# Schematic.net
KiCad netlist of a schematic drawn in Altium Designer
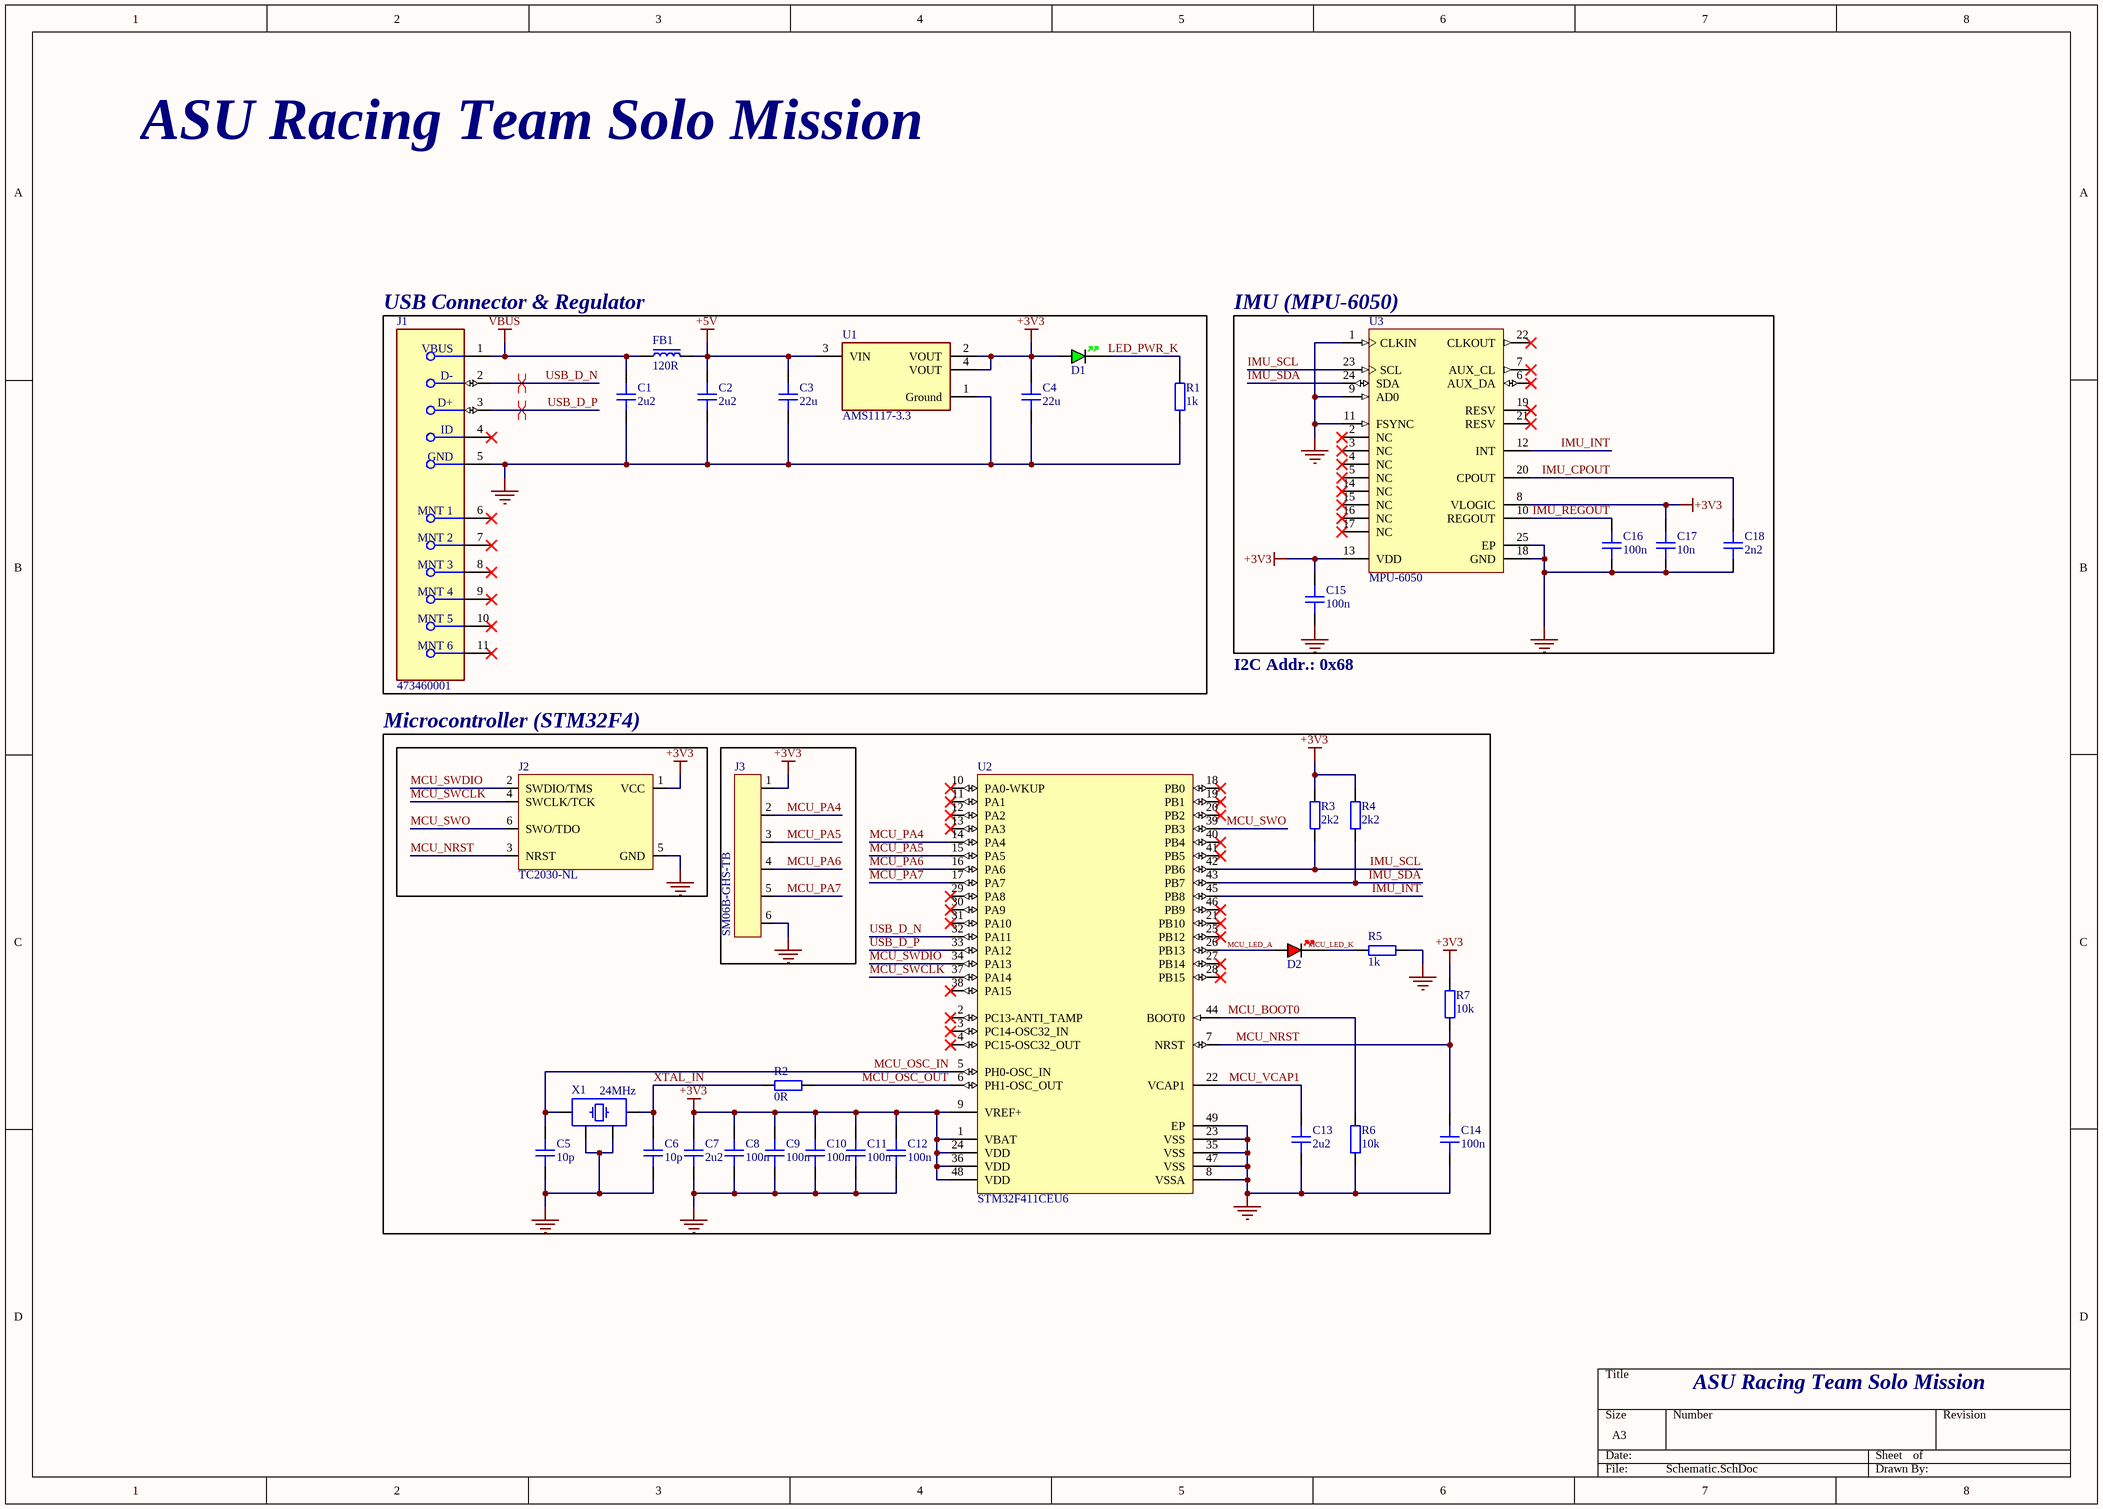
[diagram p0: Schematic.SchDoc]

(export (version "E")
  (design (tool "Eeschema 10.0.6"))
  (components
    (comp (ref "C1")
      (value "2u2")
      (footprint "CAP_0603")
      (description "Capacitor SMD 0603")
      (libsource (lib "Schematic-Lib-PhilsLab") (part "CAP_0603"))
    )
    (comp (ref "C2")
      (value "2u2")
      (footprint "CAP_0603")
      (description "Capacitor SMD 0603")
      (libsource (lib "Schematic-Lib-PhilsLab") (part "CAP_0603"))
    )
    (comp (ref "C3")
      (value "22u")
      (footprint "CAP_0805")
      (description "Capacitor SMD 0805")
      (libsource (lib "Schematic-Lib-PhilsLab") (part "CAP_0805"))
    )
    (comp (ref "C4")
      (value "22u")
      (footprint "CAP_0805")
      (description "Capacitor SMD 0805")
      (libsource (lib "Schematic-Lib-PhilsLab") (part "CAP_0805"))
    )
    (comp (ref "C5")
      (value "10p")
      (footprint "CAP_0402")
      (description "Capacitor SMD 0402")
      (libsource (lib "Schematic-Lib-PhilsLab") (part "CAP_0402"))
    )
    (comp (ref "C6")
      (value "10p")
      (footprint "CAP_0402")
      (description "Capacitor SMD 0402")
      (libsource (lib "Schematic-Lib-PhilsLab") (part "CAP_0402"))
    )
    (comp (ref "C7")
      (value "2u2")
      (footprint "CAP_0603")
      (description "Capacitor SMD 0603")
      (libsource (lib "Schematic-Lib-PhilsLab") (part "CAP_0603"))
    )
    (comp (ref "C8")
      (value "100n")
      (footprint "CAP_0402")
      (description "Capacitor SMD 0402")
      (libsource (lib "Schematic-Lib-PhilsLab") (part "CAP_0402"))
    )
    (comp (ref "C9")
      (value "100n")
      (footprint "CAP_0402")
      (description "Capacitor SMD 0402")
      (libsource (lib "Schematic-Lib-PhilsLab") (part "CAP_0402"))
    )
    (comp (ref "C10")
      (value "100n")
      (footprint "CAP_0402")
      (description "Capacitor SMD 0402")
      (libsource (lib "Schematic-Lib-PhilsLab") (part "CAP_0402"))
    )
    (comp (ref "C11")
      (value "100n")
      (footprint "CAP_0402")
      (description "Capacitor SMD 0402")
      (libsource (lib "Schematic-Lib-PhilsLab") (part "CAP_0402"))
    )
    (comp (ref "C12")
      (value "100n")
      (footprint "CAP_0402")
      (description "Capacitor SMD 0402")
      (libsource (lib "Schematic-Lib-PhilsLab") (part "CAP_0402"))
    )
    (comp (ref "C13")
      (value "2u2")
      (footprint "CAP_0603")
      (description "Capacitor SMD 0603")
      (libsource (lib "Schematic-Lib-PhilsLab") (part "CAP_0603"))
    )
    (comp (ref "C14")
      (value "100n")
      (footprint "CAP_0402")
      (description "Capacitor SMD 0402")
      (libsource (lib "Schematic-Lib-PhilsLab") (part "CAP_0402"))
    )
    (comp (ref "C15")
      (value "100n")
      (footprint "CAP_0402")
      (description "Capacitor SMD 0402")
      (libsource (lib "Schematic-Lib-PhilsLab") (part "CAP_0402"))
    )
    (comp (ref "C16")
      (value "100n")
      (footprint "CAP_0402")
      (description "Capacitor SMD 0402")
      (libsource (lib "Schematic-Lib-PhilsLab") (part "CAP_0402"))
    )
    (comp (ref "C17")
      (value "10n")
      (footprint "CAP_0402")
      (description "Capacitor SMD 0402")
      (libsource (lib "Schematic-Lib-PhilsLab") (part "CAP_0402"))
    )
    (comp (ref "C18")
      (value "2n2")
      (footprint "CAP_0402")
      (description "Capacitor SMD 0402")
      (libsource (lib "Schematic-Lib-PhilsLab") (part "CAP_0402"))
    )
    (comp (ref "D1")
      (value "GREEN")
      (footprint "LED_0402_GREEN")
      (description "LED 0402 GREEN SMD")
      (libsource (lib "Schematic-Lib-PhilsLab") (part "LED_0402_GREEN"))
    )
    (comp (ref "D2")
      (value "RED")
      (footprint "LED_0402_RED")
      (description "LED 0402 RED SMD")
      (libsource (lib "Schematic-Lib-PhilsLab") (part "LED_0402_RED"))
    )
    (comp (ref "FB1")
      (value "120R")
      (footprint "FB_0603")
      (description "Ferrite Bead SMD 0603")
      (libsource (lib "Schematic-Lib-PhilsLab") (part "FB_0603"))
    )
    (comp (ref "J1")
      (value "473460001")
      (footprint "FP-473460001-MFG")
      (description "USB - micro B USB 2.0 Receptacle Connector 5 Position Surface Mount, Right Angle")
      (fields (field (name "OCTOPART") "https://octopart.com/47346-0001-molex-7164928"))
      (libsource (lib "Altium Content Vault") (part "53ae1f1d9b557310b43ca686e5bb76a"))
    )
    (comp (ref "J2")
      (value "TC2030-NL")
      (footprint "TC2030-NL-FP")
      (description "Tag-Connect No-Solder SWD Debug Connector (No Legs) DO NOT PLACE")
      (fields
        (field (name "MANUFACTURER") "Tag-Connect")
        (field (name "MANUFACTURER PART NUMBER") "TC2030-NL-FP")
      )
      (libsource (lib "Schematic-Lib-PhilsLab") (part "TC2030-NL"))
    )
    (comp (ref "J3")
      (value "SM06B-GHS-TB")
      (footprint "SM06B-GHS-TB")
      (description "Header Connector 6 Position 1.25MM Pitch SMD Horizontal JST GH")
      (fields (field (name "MANUFACTURER") "JST"))
      (libsource (lib "Schematic-Lib-PhilsLab") (part "SM06B-GHS-TB"))
    )
    (comp (ref "R1")
      (value "1k")
      (footprint "RES_0402")
      (description "Resistor SMD 0402")
      (libsource (lib "Schematic-Lib-PhilsLab") (part "RES_0402"))
    )
    (comp (ref "R2")
      (value "0R")
      (footprint "RES_0402")
      (description "Resistor SMD 0402")
      (libsource (lib "Schematic-Lib-PhilsLab") (part "RES_0402"))
    )
    (comp (ref "R3")
      (value "2k2")
      (footprint "RES_0402")
      (description "Resistor SMD 0402")
      (libsource (lib "Schematic-Lib-PhilsLab") (part "RES_0402"))
    )
    (comp (ref "R4")
      (value "2k2")
      (footprint "RES_0402")
      (description "Resistor SMD 0402")
      (libsource (lib "Schematic-Lib-PhilsLab") (part "RES_0402"))
    )
    (comp (ref "R5")
      (value "1k")
      (footprint "RES_0402")
      (description "Resistor SMD 0402")
      (libsource (lib "Schematic-Lib-PhilsLab") (part "RES_0402"))
    )
    (comp (ref "R6")
      (value "10k")
      (footprint "RES_0402")
      (description "Resistor SMD 0402")
      (libsource (lib "Schematic-Lib-PhilsLab") (part "RES_0402"))
    )
    (comp (ref "R7")
      (value "10k")
      (footprint "RES_0402")
      (description "Resistor SMD 0402")
      (libsource (lib "Schematic-Lib-PhilsLab") (part "RES_0402"))
    )
    (comp (ref "U1")
      (value "AMS1117-3.3")
      (footprint "FP-AMS1117-IPC_C")
      (description "LDO Voltage Regulators 1A, 3.3V")
      (fields
        (field (name "OCTOPART") "https://octopart.com/ams1117-3.3-advanced+monolithic+systems-25899300")
        (field (name "MANUFACTURER") "Advanced Monolithic Systems")
      )
      (libsource (lib "Altium Content Vault") (part "8bdbb5f8e77002000e30dd2845d0354"))
    )
    (comp (ref "U2")
      (value "STM32F411CEU6")
      (footprint "STM-UFQFPN48_L")
      (libsource (lib "Altium Content Vault") (part "MC-ARM-STM32F411-UFQFPN48"))
    )
    (comp (ref "U3")
      (value "MPU-6050")
      (footprint "IS-QFN-24_V")
      (fields (field (name "MANUFACTURER") "InvenSense"))
      (libsource (lib "Altium Content Vault") (part "IS-MPU-6050-QFN-24"))
    )
    (comp (ref "X1")
      (value "24MHz")
      (footprint "XTAL_3225")
      (description "Crystal SMD 24MHz 10PPM 7pF 3225")
      (fields
        (field (name "MANUFACTURER") "Epson")
        (field (name "MANUFACTURER PART NUMBER") "TSX-3225 24.0000MF15X-AC")
      )
      (libsource (lib "Schematic-Lib-PhilsLab") (part "TSX-3225_24.0000MF15X-AC"))
    )
  )
  (nets
    (net (code "1") (name "+3V3") (class "Default")
      (node (ref "C10") (pin "2") (pinfunction "2_2") (pintype "passive"))
      (node (ref "C11") (pin "2") (pinfunction "2_2") (pintype "passive"))
      (node (ref "C12") (pin "2") (pinfunction "2_2") (pintype "passive"))
      (node (ref "C15") (pin "2") (pinfunction "2_2") (pintype "passive"))
      (node (ref "C17") (pin "2") (pinfunction "2_2") (pintype "passive"))
      (node (ref "C4") (pin "2") (pinfunction "2_2") (pintype "passive"))
      (node (ref "C7") (pin "2") (pinfunction "2_2") (pintype "passive"))
      (node (ref "C8") (pin "2") (pinfunction "2_2") (pintype "passive"))
      (node (ref "C9") (pin "2") (pinfunction "2_2") (pintype "passive"))
      (node (ref "D1") (pin "A") (pinfunction "A_A") (pintype "passive"))
      (node (ref "J2") (pin "1") (pinfunction "VCC_1") (pintype "passive"))
      (node (ref "J3") (pin "1") (pinfunction "1_1") (pintype "passive"))
      (node (ref "R3") (pin "2") (pinfunction "2_2") (pintype "passive"))
      (node (ref "R4") (pin "2") (pinfunction "2_2") (pintype "passive"))
      (node (ref "R7") (pin "2") (pinfunction "2_2") (pintype "passive"))
      (node (ref "U1") (pin "2") (pinfunction "VOUT_2") (pintype "passive"))
      (node (ref "U1") (pin "4") (pinfunction "VOUT_4") (pintype "passive"))
      (node (ref "U2") (pin "1") (pinfunction "VBAT_1") (pintype "power_in"))
      (node (ref "U2") (pin "24") (pinfunction "VDD_24") (pintype "power_in"))
      (node (ref "U2") (pin "36") (pinfunction "VDD_36") (pintype "power_in"))
      (node (ref "U2") (pin "48") (pinfunction "VDD_48") (pintype "power_in"))
      (node (ref "U2") (pin "9") (pinfunction "VREF+_9") (pintype "power_in"))
      (node (ref "U3") (pin "13") (pinfunction "VDD_13") (pintype "power_in"))
      (node (ref "U3") (pin "8") (pinfunction "VLOGIC_8") (pintype "power_in"))
    )
    (net (code "2") (name "+5V") (class "Default")
      (node (ref "C2") (pin "2") (pinfunction "2_2") (pintype "passive"))
      (node (ref "C3") (pin "2") (pinfunction "2_2") (pintype "passive"))
      (node (ref "FB1") (pin "2") (pinfunction "2_2") (pintype "passive"))
      (node (ref "U1") (pin "3") (pinfunction "VIN_3") (pintype "power_in"))
    )
    (net (code "3") (name "/IMU_CPOUT") (class "Default")
      (node (ref "C18") (pin "2") (pinfunction "2_2") (pintype "passive"))
      (node (ref "U3") (pin "20") (pinfunction "CPOUT_20") (pintype "passive"))
    )
    (net (code "4") (name "/IMU_INT") (class "Default")
      (node (ref "U2") (pin "45") (pinfunction "PB8_45") (pintype "bidirectional"))
      (node (ref "U3") (pin "12") (pinfunction "INT_12") (pintype "open_collector"))
    )
    (net (code "5") (name "/IMU_REGOUT") (class "Default")
      (node (ref "C16") (pin "2") (pinfunction "2_2") (pintype "passive"))
      (node (ref "U3") (pin "10") (pinfunction "REGOUT_10") (pintype "passive"))
    )
    (net (code "6") (name "/IMU_SCL") (class "Default")
      (node (ref "R3") (pin "1") (pinfunction "1_1") (pintype "passive"))
      (node (ref "U2") (pin "42") (pinfunction "PB6_42") (pintype "bidirectional"))
      (node (ref "U3") (pin "23") (pinfunction "SCL_23") (pintype "input"))
    )
    (net (code "7") (name "/IMU_SDA") (class "Default")
      (node (ref "R4") (pin "1") (pinfunction "1_1") (pintype "passive"))
      (node (ref "U2") (pin "43") (pinfunction "PB7_43") (pintype "bidirectional"))
      (node (ref "U3") (pin "24") (pinfunction "SDA_24") (pintype "bidirectional"))
    )
    (net (code "8") (name "/LED_PWR_K") (class "Default")
      (node (ref "D1") (pin "K") (pinfunction "K_K") (pintype "passive"))
      (node (ref "R1") (pin "2") (pinfunction "2_2") (pintype "passive"))
    )
    (net (code "9") (name "/MCU_BOOT0") (class "Default")
      (node (ref "R6") (pin "2") (pinfunction "2_2") (pintype "passive"))
      (node (ref "U2") (pin "44") (pinfunction "BOOT0_44") (pintype "input"))
    )
    (net (code "10") (name "/MCU_LED_A") (class "Default")
      (node (ref "D2") (pin "A") (pinfunction "A_A") (pintype "passive"))
      (node (ref "U2") (pin "26") (pinfunction "PB13_26") (pintype "bidirectional"))
    )
    (net (code "11") (name "/MCU_LED_K") (class "Default")
      (node (ref "D2") (pin "K") (pinfunction "K_K") (pintype "passive"))
      (node (ref "R5") (pin "2") (pinfunction "2_2") (pintype "passive"))
    )
    (net (code "12") (name "/MCU_NRST") (class "Default")
      (node (ref "C14") (pin "2") (pinfunction "2_2") (pintype "passive"))
      (node (ref "J2") (pin "3") (pinfunction "NRST_3") (pintype "passive"))
      (node (ref "R7") (pin "1") (pinfunction "1_1") (pintype "passive"))
      (node (ref "U2") (pin "7") (pinfunction "NRST_7") (pintype "bidirectional"))
    )
    (net (code "13") (name "/MCU_OSC_IN") (class "Default")
      (node (ref "C5") (pin "2") (pinfunction "2_2") (pintype "passive"))
      (node (ref "U2") (pin "5") (pinfunction "PH0-OSC_IN_5") (pintype "bidirectional"))
      (node (ref "X1") (pin "1") (pinfunction "1_1") (pintype "passive"))
    )
    (net (code "14") (name "/MCU_OSC_OUT") (class "Default")
      (node (ref "R2") (pin "2") (pinfunction "2_2") (pintype "passive"))
      (node (ref "U2") (pin "6") (pinfunction "PH1-OSC_OUT_6") (pintype "bidirectional"))
    )
    (net (code "15") (name "/MCU_PA4") (class "Default")
      (node (ref "J3") (pin "2") (pinfunction "2_2") (pintype "passive"))
      (node (ref "U2") (pin "14") (pinfunction "PA4_14") (pintype "bidirectional"))
    )
    (net (code "16") (name "/MCU_PA5") (class "Default")
      (node (ref "J3") (pin "3") (pinfunction "3_3") (pintype "passive"))
      (node (ref "U2") (pin "15") (pinfunction "PA5_15") (pintype "bidirectional"))
    )
    (net (code "17") (name "/MCU_PA6") (class "Default")
      (node (ref "J3") (pin "4") (pinfunction "4_4") (pintype "passive"))
      (node (ref "U2") (pin "16") (pinfunction "PA6_16") (pintype "bidirectional"))
    )
    (net (code "18") (name "/MCU_PA7") (class "Default")
      (node (ref "J3") (pin "5") (pinfunction "5_5") (pintype "passive"))
      (node (ref "U2") (pin "17") (pinfunction "PA7_17") (pintype "bidirectional"))
    )
    (net (code "19") (name "/MCU_SWCLK") (class "Default")
      (node (ref "J2") (pin "4") (pinfunction "SWCLK/TCK_4") (pintype "passive"))
      (node (ref "U2") (pin "37") (pinfunction "PA14_37") (pintype "bidirectional"))
    )
    (net (code "20") (name "/MCU_SWDIO") (class "Default")
      (node (ref "J2") (pin "2") (pinfunction "SWDIO/TMS_2") (pintype "passive"))
      (node (ref "U2") (pin "34") (pinfunction "PA13_34") (pintype "bidirectional"))
    )
    (net (code "21") (name "/MCU_SWO") (class "Default")
      (node (ref "J2") (pin "6") (pinfunction "SWO/TDO_6") (pintype "passive"))
      (node (ref "U2") (pin "39") (pinfunction "PB3_39") (pintype "bidirectional"))
    )
    (net (code "22") (name "/MCU_VCAP1") (class "Default")
      (node (ref "C13") (pin "2") (pinfunction "2_2") (pintype "passive"))
      (node (ref "U2") (pin "22") (pinfunction "VCAP1_22") (pintype "passive"))
    )
    (net (code "23") (name "/USB_D_N") (class "Default")
      (node (ref "J1") (pin "2") (pinfunction "D-_2") (pintype "bidirectional"))
      (node (ref "U2") (pin "32") (pinfunction "PA11_32") (pintype "bidirectional"))
    )
    (net (code "24") (name "/USB_D_P") (class "Default")
      (node (ref "J1") (pin "3") (pinfunction "D+_3") (pintype "bidirectional"))
      (node (ref "U2") (pin "33") (pinfunction "PA12_33") (pintype "bidirectional"))
    )
    (net (code "25") (name "/XTAL_IN") (class "Default")
      (node (ref "C6") (pin "2") (pinfunction "2_2") (pintype "passive"))
      (node (ref "R2") (pin "1") (pinfunction "1_1") (pintype "passive"))
      (node (ref "X1") (pin "3") (pinfunction "3_3") (pintype "passive"))
    )
    (net (code "26") (name "GND") (class "Default")
      (node (ref "C1") (pin "1") (pinfunction "1_1") (pintype "passive"))
      (node (ref "C10") (pin "1") (pinfunction "1_1") (pintype "passive"))
      (node (ref "C11") (pin "1") (pinfunction "1_1") (pintype "passive"))
      (node (ref "C12") (pin "1") (pinfunction "1_1") (pintype "passive"))
      (node (ref "C13") (pin "1") (pinfunction "1_1") (pintype "passive"))
      (node (ref "C14") (pin "1") (pinfunction "1_1") (pintype "passive"))
      (node (ref "C15") (pin "1") (pinfunction "1_1") (pintype "passive"))
      (node (ref "C16") (pin "1") (pinfunction "1_1") (pintype "passive"))
      (node (ref "C17") (pin "1") (pinfunction "1_1") (pintype "passive"))
      (node (ref "C18") (pin "1") (pinfunction "1_1") (pintype "passive"))
      (node (ref "C2") (pin "1") (pinfunction "1_1") (pintype "passive"))
      (node (ref "C3") (pin "1") (pinfunction "1_1") (pintype "passive"))
      (node (ref "C4") (pin "1") (pinfunction "1_1") (pintype "passive"))
      (node (ref "C5") (pin "1") (pinfunction "1_1") (pintype "passive"))
      (node (ref "C6") (pin "1") (pinfunction "1_1") (pintype "passive"))
      (node (ref "C7") (pin "1") (pinfunction "1_1") (pintype "passive"))
      (node (ref "C8") (pin "1") (pinfunction "1_1") (pintype "passive"))
      (node (ref "C9") (pin "1") (pinfunction "1_1") (pintype "passive"))
      (node (ref "J1") (pin "5") (pinfunction "GND_5") (pintype "power_in"))
      (node (ref "J2") (pin "5") (pinfunction "GND_5") (pintype "passive"))
      (node (ref "J3") (pin "6") (pinfunction "6_6") (pintype "passive"))
      (node (ref "R1") (pin "1") (pinfunction "1_1") (pintype "passive"))
      (node (ref "R5") (pin "1") (pinfunction "1_1") (pintype "passive"))
      (node (ref "R6") (pin "1") (pinfunction "1_1") (pintype "passive"))
      (node (ref "U1") (pin "1") (pinfunction "Ground_1") (pintype "power_in"))
      (node (ref "U2") (pin "23") (pinfunction "VSS_23") (pintype "power_in"))
      (node (ref "U2") (pin "35") (pinfunction "VSS_35") (pintype "power_in"))
      (node (ref "U2") (pin "47") (pinfunction "VSS_47") (pintype "power_in"))
      (node (ref "U2") (pin "49") (pinfunction "EP_49") (pintype "power_in"))
      (node (ref "U2") (pin "8") (pinfunction "VSSA_8") (pintype "power_in"))
      (node (ref "U3") (pin "1") (pinfunction "CLKIN_1") (pintype "input"))
      (node (ref "U3") (pin "11") (pinfunction "FSYNC_11") (pintype "input"))
      (node (ref "U3") (pin "18") (pinfunction "GND_18") (pintype "power_in"))
      (node (ref "U3") (pin "25") (pinfunction "EP_25") (pintype "power_in"))
      (node (ref "U3") (pin "9") (pinfunction "AD0_9") (pintype "input"))
      (node (ref "X1") (pin "2") (pinfunction "2_2") (pintype "passive"))
      (node (ref "X1") (pin "4") (pinfunction "4_4") (pintype "passive"))
    )
    (net (code "27") (name "VBUS") (class "Default")
      (node (ref "C1") (pin "2") (pinfunction "2_2") (pintype "passive"))
      (node (ref "FB1") (pin "1") (pinfunction "1_1") (pintype "passive"))
      (node (ref "J1") (pin "1") (pinfunction "VBUS_1") (pintype "power_in"))
    )
    (net (code "28") (name "unconnected-(J1-ID-Pad4)") (class "Default")
      (node (ref "J1") (pin "4") (pinfunction "ID_4") (pintype "passive+no_connect"))
    )
    (net (code "29") (name "unconnected-(J1-MNT_1-Pad6)") (class "Default")
      (node (ref "J1") (pin "6") (pinfunction "MNT_1_6") (pintype "passive+no_connect"))
    )
    (net (code "30") (name "unconnected-(J1-MNT_2-Pad7)") (class "Default")
      (node (ref "J1") (pin "7") (pinfunction "MNT_2_7") (pintype "passive+no_connect"))
    )
    (net (code "31") (name "unconnected-(J1-MNT_3-Pad8)") (class "Default")
      (node (ref "J1") (pin "8") (pinfunction "MNT_3_8") (pintype "passive+no_connect"))
    )
    (net (code "32") (name "unconnected-(J1-MNT_4-Pad9)") (class "Default")
      (node (ref "J1") (pin "9") (pinfunction "MNT_4_9") (pintype "passive+no_connect"))
    )
    (net (code "33") (name "unconnected-(J1-MNT_5-Pad10)") (class "Default")
      (node (ref "J1") (pin "10") (pinfunction "MNT_5_10") (pintype "passive+no_connect"))
    )
    (net (code "34") (name "unconnected-(J1-MNT_6-Pad11)") (class "Default")
      (node (ref "J1") (pin "11") (pinfunction "MNT_6_11") (pintype "passive+no_connect"))
    )
    (net (code "35") (name "unconnected-(U2-PA0-WKUP-Pad10)") (class "Default")
      (node (ref "U2") (pin "10") (pinfunction "PA0-WKUP_10") (pintype "bidirectional+no_connect"))
    )
    (net (code "36") (name "unconnected-(U2-PA1-Pad11)") (class "Default")
      (node (ref "U2") (pin "11") (pinfunction "PA1_11") (pintype "bidirectional+no_connect"))
    )
    (net (code "37") (name "unconnected-(U2-PA2-Pad12)") (class "Default")
      (node (ref "U2") (pin "12") (pinfunction "PA2_12") (pintype "bidirectional+no_connect"))
    )
    (net (code "38") (name "unconnected-(U2-PA3-Pad13)") (class "Default")
      (node (ref "U2") (pin "13") (pinfunction "PA3_13") (pintype "bidirectional+no_connect"))
    )
    (net (code "39") (name "unconnected-(U2-PA8-Pad29)") (class "Default")
      (node (ref "U2") (pin "29") (pinfunction "PA8_29") (pintype "bidirectional+no_connect"))
    )
    (net (code "40") (name "unconnected-(U2-PA9-Pad30)") (class "Default")
      (node (ref "U2") (pin "30") (pinfunction "PA9_30") (pintype "bidirectional+no_connect"))
    )
    (net (code "41") (name "unconnected-(U2-PA10-Pad31)") (class "Default")
      (node (ref "U2") (pin "31") (pinfunction "PA10_31") (pintype "bidirectional+no_connect"))
    )
    (net (code "42") (name "unconnected-(U2-PA15-Pad38)") (class "Default")
      (node (ref "U2") (pin "38") (pinfunction "PA15_38") (pintype "bidirectional+no_connect"))
    )
    (net (code "43") (name "unconnected-(U2-PB0-Pad18)") (class "Default")
      (node (ref "U2") (pin "18") (pinfunction "PB0_18") (pintype "bidirectional+no_connect"))
    )
    (net (code "44") (name "unconnected-(U2-PB1-Pad19)") (class "Default")
      (node (ref "U2") (pin "19") (pinfunction "PB1_19") (pintype "bidirectional+no_connect"))
    )
    (net (code "45") (name "unconnected-(U2-PB2-Pad20)") (class "Default")
      (node (ref "U2") (pin "20") (pinfunction "PB2_20") (pintype "bidirectional+no_connect"))
    )
    (net (code "46") (name "unconnected-(U2-PB4-Pad40)") (class "Default")
      (node (ref "U2") (pin "40") (pinfunction "PB4_40") (pintype "bidirectional+no_connect"))
    )
    (net (code "47") (name "unconnected-(U2-PB5-Pad41)") (class "Default")
      (node (ref "U2") (pin "41") (pinfunction "PB5_41") (pintype "bidirectional+no_connect"))
    )
    (net (code "48") (name "unconnected-(U2-PB9-Pad46)") (class "Default")
      (node (ref "U2") (pin "46") (pinfunction "PB9_46") (pintype "bidirectional+no_connect"))
    )
    (net (code "49") (name "unconnected-(U2-PB10-Pad21)") (class "Default")
      (node (ref "U2") (pin "21") (pinfunction "PB10_21") (pintype "bidirectional+no_connect"))
    )
    (net (code "50") (name "unconnected-(U2-PB12-Pad25)") (class "Default")
      (node (ref "U2") (pin "25") (pinfunction "PB12_25") (pintype "bidirectional+no_connect"))
    )
    (net (code "51") (name "unconnected-(U2-PB14-Pad27)") (class "Default")
      (node (ref "U2") (pin "27") (pinfunction "PB14_27") (pintype "bidirectional+no_connect"))
    )
    (net (code "52") (name "unconnected-(U2-PB15-Pad28)") (class "Default")
      (node (ref "U2") (pin "28") (pinfunction "PB15_28") (pintype "bidirectional+no_connect"))
    )
    (net (code "53") (name "unconnected-(U2-PC13-ANTI_TAMP-Pad2)") (class "Default")
      (node (ref "U2") (pin "2") (pinfunction "PC13-ANTI_TAMP_2") (pintype "bidirectional+no_connect"))
    )
    (net (code "54") (name "unconnected-(U2-PC14-OSC32_IN-Pad3)") (class "Default")
      (node (ref "U2") (pin "3") (pinfunction "PC14-OSC32_IN_3") (pintype "bidirectional+no_connect"))
    )
    (net (code "55") (name "unconnected-(U2-PC15-OSC32_OUT-Pad4)") (class "Default")
      (node (ref "U2") (pin "4") (pinfunction "PC15-OSC32_OUT_4") (pintype "bidirectional+no_connect"))
    )
    (net (code "56") (name "unconnected-(U3-AUX_CL-Pad7)") (class "Default")
      (node (ref "U3") (pin "7") (pinfunction "AUX_CL_7") (pintype "output+no_connect"))
    )
    (net (code "57") (name "unconnected-(U3-AUX_DA-Pad6)") (class "Default")
      (node (ref "U3") (pin "6") (pinfunction "AUX_DA_6") (pintype "bidirectional+no_connect"))
    )
    (net (code "58") (name "unconnected-(U3-CLKOUT-Pad22)") (class "Default")
      (node (ref "U3") (pin "22") (pinfunction "CLKOUT_22") (pintype "output+no_connect"))
    )
    (net (code "59") (name "unconnected-(U3-NC-Pad2)") (class "Default")
      (node (ref "U3") (pin "2") (pinfunction "NC_2") (pintype "passive+no_connect"))
    )
    (net (code "60") (name "unconnected-(U3-NC-Pad3)") (class "Default")
      (node (ref "U3") (pin "3") (pinfunction "NC_3") (pintype "passive+no_connect"))
    )
    (net (code "61") (name "unconnected-(U3-NC-Pad4)") (class "Default")
      (node (ref "U3") (pin "4") (pinfunction "NC_4") (pintype "passive+no_connect"))
    )
    (net (code "62") (name "unconnected-(U3-NC-Pad5)") (class "Default")
      (node (ref "U3") (pin "5") (pinfunction "NC_5") (pintype "passive+no_connect"))
    )
    (net (code "63") (name "unconnected-(U3-NC-Pad14)") (class "Default")
      (node (ref "U3") (pin "14") (pinfunction "NC_14") (pintype "passive+no_connect"))
    )
    (net (code "64") (name "unconnected-(U3-NC-Pad15)") (class "Default")
      (node (ref "U3") (pin "15") (pinfunction "NC_15") (pintype "passive+no_connect"))
    )
    (net (code "65") (name "unconnected-(U3-NC-Pad16)") (class "Default")
      (node (ref "U3") (pin "16") (pinfunction "NC_16") (pintype "passive+no_connect"))
    )
    (net (code "66") (name "unconnected-(U3-NC-Pad17)") (class "Default")
      (node (ref "U3") (pin "17") (pinfunction "NC_17") (pintype "passive+no_connect"))
    )
    (net (code "67") (name "unconnected-(U3-RESV-Pad19)") (class "Default")
      (node (ref "U3") (pin "19") (pinfunction "RESV_19") (pintype "passive+no_connect"))
    )
    (net (code "68") (name "unconnected-(U3-RESV-Pad21)") (class "Default")
      (node (ref "U3") (pin "21") (pinfunction "RESV_21") (pintype "passive+no_connect"))
    )
  )
)
